# kitt_0805.net
KiCad netlist of a schematic drawn in EAGLE
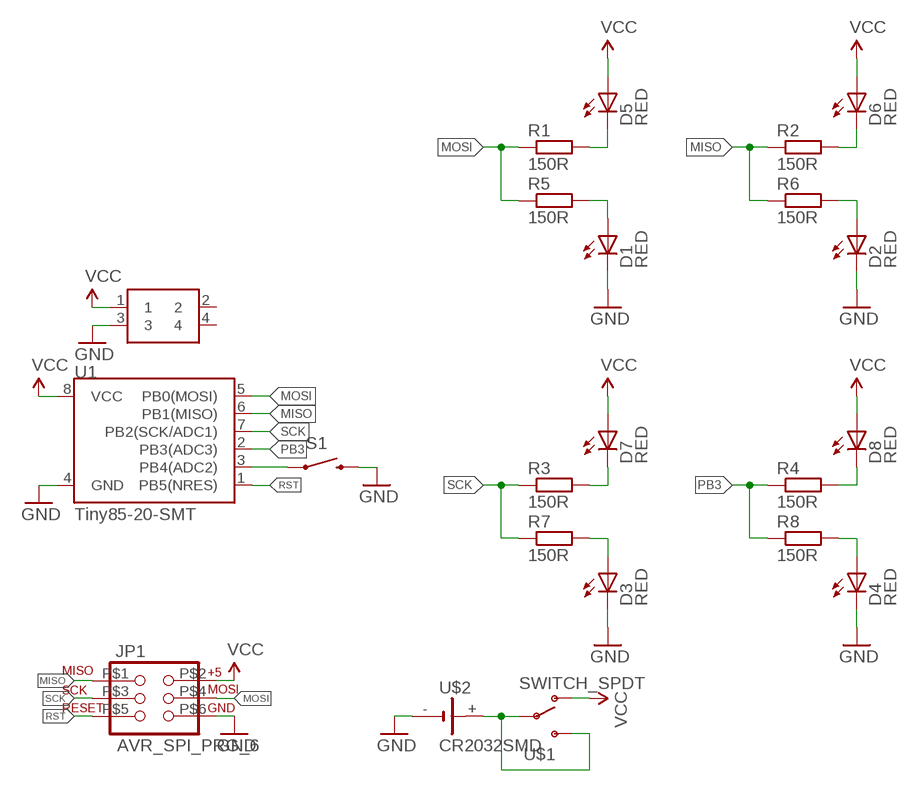
[diagram p0: schematic, sheet 1]

(export (version "E")
  (design (tool "Eeschema 10.0.6"))
  (components
    (comp (ref "D1")
      (value "RED")
      (footprint "eagle-import:CHIP-LED0805")
      (libsource (lib "eagle-import") (part "LEDCHIP-LED0805"))
    )
    (comp (ref "D2")
      (value "RED")
      (footprint "eagle-import:CHIP-LED0805")
      (libsource (lib "eagle-import") (part "LEDCHIP-LED0805"))
    )
    (comp (ref "D3")
      (value "RED")
      (footprint "eagle-import:CHIP-LED0805")
      (libsource (lib "eagle-import") (part "LEDCHIP-LED0805"))
    )
    (comp (ref "D4")
      (value "RED")
      (footprint "eagle-import:CHIP-LED0805")
      (libsource (lib "eagle-import") (part "LEDCHIP-LED0805"))
    )
    (comp (ref "D5")
      (value "RED")
      (footprint "eagle-import:CHIP-LED0805")
      (libsource (lib "eagle-import") (part "LEDCHIP-LED0805"))
    )
    (comp (ref "D6")
      (value "RED")
      (footprint "eagle-import:CHIP-LED0805")
      (libsource (lib "eagle-import") (part "LEDCHIP-LED0805"))
    )
    (comp (ref "D7")
      (value "RED")
      (footprint "eagle-import:CHIP-LED0805")
      (libsource (lib "eagle-import") (part "LEDCHIP-LED0805"))
    )
    (comp (ref "D8")
      (value "RED")
      (footprint "eagle-import:CHIP-LED0805")
      (libsource (lib "eagle-import") (part "LEDCHIP-LED0805"))
    )
    (comp (ref "JP1")
      (value "AVR_SPI_PRG_6")
      (footprint "eagle-import:2X3_SMD_PAD")
      (libsource (lib "eagle-import") (part "AVR_SPI_PRG_6"))
    )
    (comp (ref "R1")
      (value "150R")
      (footprint "eagle-import:M0805")
      (libsource (lib "eagle-import") (part "R-EU_M0805"))
    )
    (comp (ref "R2")
      (value "150R")
      (footprint "eagle-import:M0805")
      (libsource (lib "eagle-import") (part "R-EU_M0805"))
    )
    (comp (ref "R3")
      (value "150R")
      (footprint "eagle-import:M0805")
      (libsource (lib "eagle-import") (part "R-EU_M0805"))
    )
    (comp (ref "R4")
      (value "150R")
      (footprint "eagle-import:M0805")
      (libsource (lib "eagle-import") (part "R-EU_M0805"))
    )
    (comp (ref "R5")
      (value "150R")
      (footprint "eagle-import:M0805")
      (libsource (lib "eagle-import") (part "R-EU_M0805"))
    )
    (comp (ref "R6")
      (value "150R")
      (footprint "eagle-import:M0805")
      (libsource (lib "eagle-import") (part "R-EU_M0805"))
    )
    (comp (ref "R7")
      (value "150R")
      (footprint "eagle-import:M0805")
      (libsource (lib "eagle-import") (part "R-EU_M0805"))
    )
    (comp (ref "R8")
      (value "150R")
      (footprint "eagle-import:M0805")
      (libsource (lib "eagle-import") (part "R-EU_M0805"))
    )
    (comp (ref "S1")
      (value "SWITCH-MOMENTARY-2-SMD-1101NE")
      (footprint "eagle-import:TACTILE-SWITCH-1101NE")
      (libsource (lib "eagle-import") (part "SWITCH-MOMENTARY-2-SMD-1101NE"))
    )
    (comp (ref "U$1")
      (value "SWITCH_SPDT")
      (footprint "eagle-import:KPS-1290")
      (libsource (lib "eagle-import") (part "SWITCH_SPDT"))
    )
    (comp (ref "U$2")
      (value "CR2032SMD")
      (footprint "eagle-import:CR2032SMD")
      (libsource (lib "eagle-import") (part "CR2032SMD"))
    )
    (comp (ref "U$4")
      (value "2X2-SMT")
      (footprint "eagle-import:2X2-SMT")
      (libsource (lib "eagle-import") (part "2X2-SMT"))
    )
    (comp (ref "U1")
      (value "Tiny85-20-SMT")
      (footprint "eagle-import:SO08-EIAJ")
      (libsource (lib "eagle-import") (part "ATTINY45TINY85-20-SMT"))
    )
  )
  (nets
    (net (code "1") (name "GND") (class "Default")
      (node (ref "D1") (pin "C") (pinfunction "C_C") (pintype "passive"))
      (node (ref "D2") (pin "C") (pinfunction "C_C") (pintype "passive"))
      (node (ref "D3") (pin "C") (pinfunction "C_C") (pintype "passive"))
      (node (ref "D4") (pin "C") (pinfunction "C_C") (pintype "passive"))
      (node (ref "JP1") (pin "P$6") (pinfunction "6_P$6") (pintype "passive"))
      (node (ref "S1") (pin "P$2") (pinfunction "2_P$2") (pintype "passive"))
      (node (ref "U$2") (pin "-") (pinfunction "-_-") (pintype "passive"))
      (node (ref "U$4") (pin "3") (pinfunction "3_3") (pintype "bidirectional"))
      (node (ref "U1") (pin "4") (pinfunction "GND_4") (pintype "bidirectional"))
    )
    (net (code "2") (name "MISO") (class "Default")
      (node (ref "JP1") (pin "P$1") (pinfunction "1_P$1") (pintype "passive"))
      (node (ref "R2") (pin "1") (pinfunction "1_1") (pintype "passive"))
      (node (ref "R6") (pin "1") (pinfunction "1_1") (pintype "passive"))
      (node (ref "U1") (pin "6") (pinfunction "PB1(MISO)_6") (pintype "bidirectional"))
    )
    (net (code "3") (name "MOSI") (class "Default")
      (node (ref "JP1") (pin "P$4") (pinfunction "4_P$4") (pintype "passive"))
      (node (ref "R1") (pin "1") (pinfunction "1_1") (pintype "passive"))
      (node (ref "R5") (pin "1") (pinfunction "1_1") (pintype "passive"))
      (node (ref "U1") (pin "5") (pinfunction "PB0(MOSI)_5") (pintype "bidirectional"))
    )
    (net (code "4") (name "Net-(D1-PadA)") (class "Default")
      (node (ref "D1") (pin "A") (pinfunction "A_A") (pintype "passive"))
      (node (ref "R5") (pin "2") (pinfunction "2_2") (pintype "passive"))
    )
    (net (code "5") (name "Net-(D2-PadA)") (class "Default")
      (node (ref "D2") (pin "A") (pinfunction "A_A") (pintype "passive"))
      (node (ref "R6") (pin "2") (pinfunction "2_2") (pintype "passive"))
    )
    (net (code "6") (name "Net-(D3-PadA)") (class "Default")
      (node (ref "D3") (pin "A") (pinfunction "A_A") (pintype "passive"))
      (node (ref "R7") (pin "2") (pinfunction "2_2") (pintype "passive"))
    )
    (net (code "7") (name "Net-(D4-PadA)") (class "Default")
      (node (ref "D4") (pin "A") (pinfunction "A_A") (pintype "passive"))
      (node (ref "R8") (pin "2") (pinfunction "2_2") (pintype "passive"))
    )
    (net (code "8") (name "Net-(D5-PadC)") (class "Default")
      (node (ref "D5") (pin "C") (pinfunction "C_C") (pintype "passive"))
      (node (ref "R1") (pin "2") (pinfunction "2_2") (pintype "passive"))
    )
    (net (code "9") (name "Net-(D6-PadC)") (class "Default")
      (node (ref "D6") (pin "C") (pinfunction "C_C") (pintype "passive"))
      (node (ref "R2") (pin "2") (pinfunction "2_2") (pintype "passive"))
    )
    (net (code "10") (name "Net-(D7-PadC)") (class "Default")
      (node (ref "D7") (pin "C") (pinfunction "C_C") (pintype "passive"))
      (node (ref "R3") (pin "2") (pinfunction "2_2") (pintype "passive"))
    )
    (net (code "11") (name "Net-(D8-PadC)") (class "Default")
      (node (ref "D8") (pin "C") (pinfunction "C_C") (pintype "passive"))
      (node (ref "R4") (pin "2") (pinfunction "2_2") (pintype "passive"))
    )
    (net (code "12") (name "Net-(S1-1)") (class "Default")
      (node (ref "S1") (pin "P$1") (pinfunction "1_P$1") (pintype "passive"))
      (node (ref "U1") (pin "3") (pinfunction "PB4(ADC2)_3") (pintype "bidirectional"))
    )
    (net (code "13") (name "Net-(U$1-PadP)") (class "Default")
      (node (ref "U$1") (pin "P") (pinfunction "P_P") (pintype "passive"))
      (node (ref "U$1") (pin "S") (pinfunction "S_S") (pintype "passive"))
      (node (ref "U$2") (pin "+") (pinfunction "+_+") (pintype "passive"))
    )
    (net (code "14") (name "PB3") (class "Default")
      (node (ref "R4") (pin "1") (pinfunction "1_1") (pintype "passive"))
      (node (ref "R8") (pin "1") (pinfunction "1_1") (pintype "passive"))
      (node (ref "U1") (pin "2") (pinfunction "PB3(ADC3)_2") (pintype "bidirectional"))
    )
    (net (code "15") (name "RST") (class "Default")
      (node (ref "JP1") (pin "P$5") (pinfunction "5_P$5") (pintype "passive"))
      (node (ref "U1") (pin "1") (pinfunction "PB5(NRES)_1") (pintype "bidirectional"))
    )
    (net (code "16") (name "SCK") (class "Default")
      (node (ref "JP1") (pin "P$3") (pinfunction "3_P$3") (pintype "passive"))
      (node (ref "R3") (pin "1") (pinfunction "1_1") (pintype "passive"))
      (node (ref "R7") (pin "1") (pinfunction "1_1") (pintype "passive"))
      (node (ref "U1") (pin "7") (pinfunction "PB2(SCK/ADC1)_7") (pintype "bidirectional"))
    )
    (net (code "17") (name "VCC") (class "Default")
      (node (ref "D5") (pin "A") (pinfunction "A_A") (pintype "passive"))
      (node (ref "D6") (pin "A") (pinfunction "A_A") (pintype "passive"))
      (node (ref "D7") (pin "A") (pinfunction "A_A") (pintype "passive"))
      (node (ref "D8") (pin "A") (pinfunction "A_A") (pintype "passive"))
      (node (ref "JP1") (pin "P$2") (pinfunction "2_P$2") (pintype "passive"))
      (node (ref "U$1") (pin "O") (pinfunction "O_O") (pintype "passive"))
      (node (ref "U$4") (pin "1") (pinfunction "1_1") (pintype "bidirectional"))
      (node (ref "U1") (pin "8") (pinfunction "VCC_8") (pintype "bidirectional"))
    )
    (net (code "18") (name "unconnected-(U$4-Pad2)") (class "Default")
      (node (ref "U$4") (pin "2") (pinfunction "2_2") (pintype "bidirectional"))
    )
    (net (code "19") (name "unconnected-(U$4-Pad4)") (class "Default")
      (node (ref "U$4") (pin "4") (pinfunction "4_4") (pintype "bidirectional"))
    )
  )
)
